# main.net
KiCad netlist of a schematic drawn in EAGLE
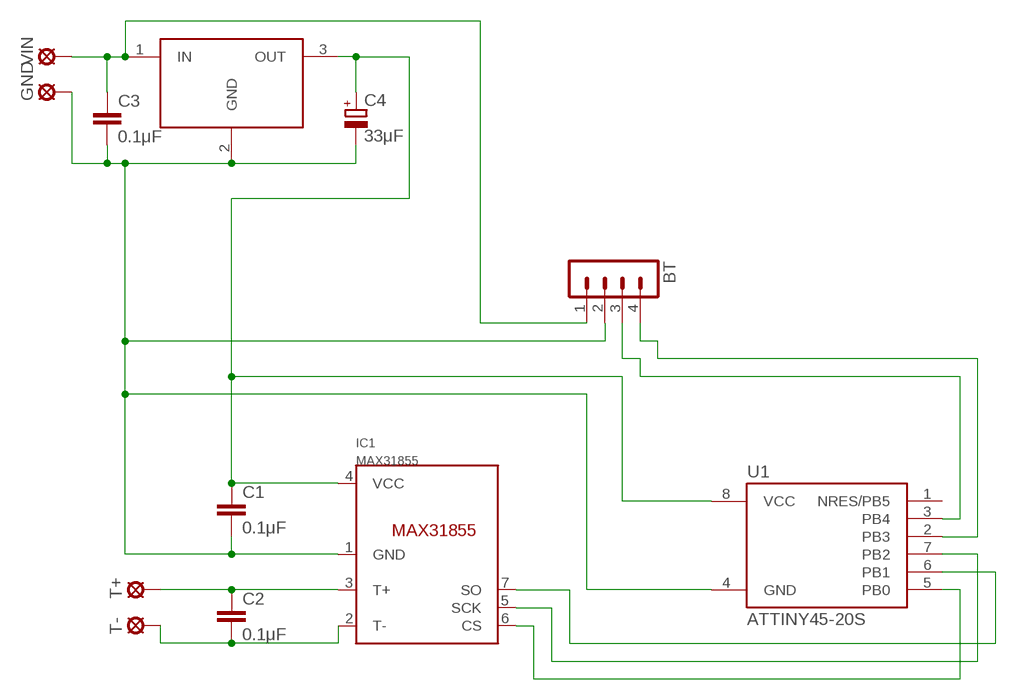
[diagram p0: schematic, sheet 1]

(export (version "E")
  (design (tool "Eeschema 10.0.6"))
  (components
    (comp (ref "BT")
      (value "MA04-1")
      (footprint "eagle-import:MA04-1")
      (libsource (lib "eagle-import") (part "MA04-1"))
    )
    (comp (ref "C1")
      (value "0.1μF")
      (footprint "eagle-import:C1206")
      (libsource (lib "eagle-import") (part "C-EUC1206"))
    )
    (comp (ref "C2")
      (value "0.1μF")
      (footprint "eagle-import:C1206")
      (libsource (lib "eagle-import") (part "C-EUC1206"))
    )
    (comp (ref "C3")
      (value "0.1μF")
      (footprint "eagle-import:C1206")
      (libsource (lib "eagle-import") (part "C-EUC1206"))
    )
    (comp (ref "C4")
      (value "33μF")
      (footprint "eagle-import:E1,8-4")
      (libsource (lib "eagle-import") (part "CPOL-EUE1.8-4"))
    )
    (comp (ref "GND")
      (value "LSP13")
      (footprint "eagle-import:LSP13")
      (libsource (lib "eagle-import") (part "LSP13"))
    )
    (comp (ref "IC1")
      (value "MAX31855")
      (footprint "eagle-import:SOIC8")
      (libsource (lib "eagle-import") (part "MAX31855"))
    )
    (comp (ref "IC2")
      (value "LM3940IMP-3.3")
      (footprint "eagle-import:SOT223")
      (libsource (lib "eagle-import") (part "LM3940IMP-3.3"))
    )
    (comp (ref "T+")
      (value "LSP13")
      (footprint "eagle-import:LSP13")
      (libsource (lib "eagle-import") (part "LSP13"))
    )
    (comp (ref "T-")
      (value "LSP13")
      (footprint "eagle-import:LSP13")
      (libsource (lib "eagle-import") (part "LSP13"))
    )
    (comp (ref "U1")
      (value "ATTINY45-20S")
      (footprint "eagle-import:SOIC8_EIAJ_208MIL")
      (libsource (lib "eagle-import") (part "ATTINY45S-20"))
    )
    (comp (ref "VIN")
      (value "LSP13")
      (footprint "eagle-import:LSP13")
      (libsource (lib "eagle-import") (part "LSP13"))
    )
  )
  (nets
    (net (code "1") (name "Net-(IC1-CS)") (class "Default")
      (node (ref "IC1") (pin "6") (pinfunction "CS_6") (pintype "input"))
      (node (ref "U1") (pin "5") (pinfunction "PB0_5") (pintype "bidirectional"))
    )
    (net (code "2") (name "Net-(IC1-GND)") (class "Default")
      (node (ref "BT") (pin "2") (pinfunction "2_2") (pintype "passive"))
      (node (ref "C1") (pin "2") (pinfunction "2_2") (pintype "passive"))
      (node (ref "C3") (pin "2") (pinfunction "2_2") (pintype "passive"))
      (node (ref "C4") (pin "-") (pinfunction "-_-") (pintype "passive"))
      (node (ref "GND") (pin "MP") (pinfunction "MP_MP") (pintype "passive"))
      (node (ref "IC1") (pin "1") (pinfunction "GND_1") (pintype "power_in"))
      (node (ref "IC2") (pin "2") (pinfunction "GND_2") (pintype "power_in"))
      (node (ref "U1") (pin "4") (pinfunction "GND_4") (pintype "power_in"))
    )
    (net (code "3") (name "Net-(IC1-SCK)") (class "Default")
      (node (ref "IC1") (pin "5") (pinfunction "SCK_5") (pintype "input"))
      (node (ref "U1") (pin "7") (pinfunction "PB2_7") (pintype "bidirectional"))
    )
    (net (code "4") (name "Net-(IC1-SO)") (class "Default")
      (node (ref "IC1") (pin "7") (pinfunction "SO_7") (pintype "output"))
      (node (ref "U1") (pin "6") (pinfunction "PB1_6") (pintype "bidirectional"))
    )
    (net (code "5") (name "Net-(IC1-T+)") (class "Default")
      (node (ref "C2") (pin "1") (pinfunction "1_1") (pintype "passive"))
      (node (ref "IC1") (pin "3") (pinfunction "T+_3") (pintype "input"))
      (node (ref "T+") (pin "MP") (pinfunction "MP_MP") (pintype "passive"))
    )
    (net (code "6") (name "Net-(IC1-T-)") (class "Default")
      (node (ref "C2") (pin "2") (pinfunction "2_2") (pintype "passive"))
      (node (ref "IC1") (pin "2") (pinfunction "T-_2") (pintype "input"))
      (node (ref "T-") (pin "MP") (pinfunction "MP_MP") (pintype "passive"))
    )
    (net (code "7") (name "Net-(IC1-VCC)") (class "Default")
      (node (ref "C1") (pin "1") (pinfunction "1_1") (pintype "passive"))
      (node (ref "C4") (pin "+") (pinfunction "+_+") (pintype "passive"))
      (node (ref "IC1") (pin "4") (pinfunction "VCC_4") (pintype "power_in"))
      (node (ref "IC2") (pin "3") (pinfunction "OUT_3") (pintype "power_in"))
      (node (ref "U1") (pin "8") (pinfunction "VCC_8") (pintype "power_in"))
    )
    (net (code "8") (name "Net-(IC2-IN)") (class "Default")
      (node (ref "BT") (pin "1") (pinfunction "1_1") (pintype "passive"))
      (node (ref "C3") (pin "1") (pinfunction "1_1") (pintype "passive"))
      (node (ref "IC2") (pin "1") (pinfunction "IN_1") (pintype "power_in"))
      (node (ref "VIN") (pin "MP") (pinfunction "MP_MP") (pintype "passive"))
    )
    (net (code "9") (name "Net-(U1-PB3)") (class "Default")
      (node (ref "BT") (pin "4") (pinfunction "4_4") (pintype "passive"))
      (node (ref "U1") (pin "2") (pinfunction "PB3_2") (pintype "bidirectional"))
    )
    (net (code "10") (name "Net-(U1-PB4)") (class "Default")
      (node (ref "BT") (pin "3") (pinfunction "3_3") (pintype "passive"))
      (node (ref "U1") (pin "3") (pinfunction "PB4_3") (pintype "bidirectional"))
    )
    (net (code "11") (name "unconnected-(U1-NRES{slash}PB5-Pad1)") (class "Default")
      (node (ref "U1") (pin "1") (pinfunction "NRES/PB5_1") (pintype "bidirectional"))
    )
  )
)
